# Connector.net
KiCad netlist of a schematic drawn in Altium Designer
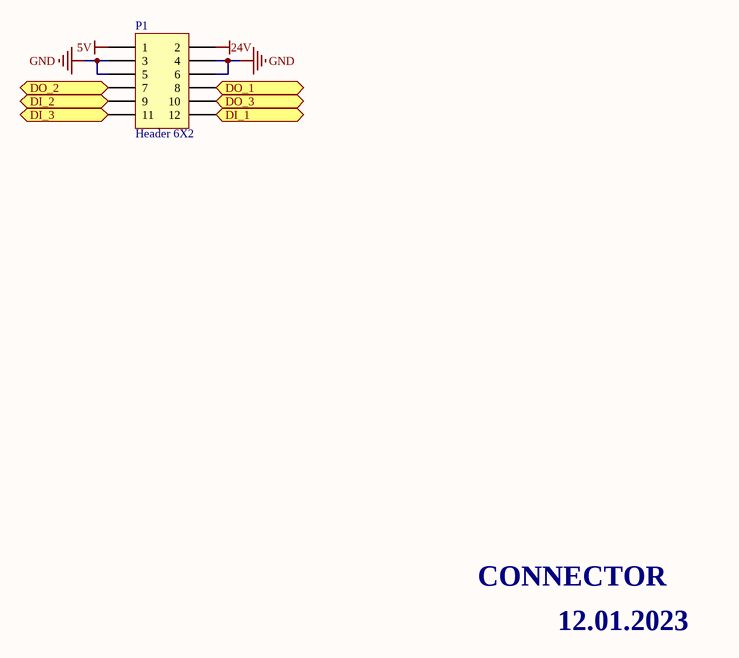
[diagram p0: Connector.SchDoc]

(export (version "E")
  (design (tool "Eeschema 10.0.6"))
  (components
    (comp (ref "P1")
      (value "Header 6X2")
      (footprint "HDR2X6")
      (description "CONNECTOR Header, 6-Pin, Dual row")
      (fields (field (name "PUBLISHER") "Altium Limited"))
      (libsource (lib "geolib") (part "Header 6X2"))
    )
  )
  (nets
    (net (code "1") (name "/DI_1") (class "Default")
      (node (ref "P1") (pin "12") (pinfunction "12_12") (pintype "passive"))
    )
    (net (code "2") (name "/DI_2") (class "Default")
      (node (ref "P1") (pin "9") (pinfunction "9_9") (pintype "passive"))
    )
    (net (code "3") (name "/DI_3") (class "Default")
      (node (ref "P1") (pin "11") (pinfunction "11_11") (pintype "passive"))
    )
    (net (code "4") (name "/DO_1") (class "Default")
      (node (ref "P1") (pin "8") (pinfunction "8_8") (pintype "passive"))
    )
    (net (code "5") (name "/DO_2") (class "Default")
      (node (ref "P1") (pin "7") (pinfunction "7_7") (pintype "passive"))
    )
    (net (code "6") (name "/DO_3") (class "Default")
      (node (ref "P1") (pin "10") (pinfunction "10_10") (pintype "passive"))
    )
    (net (code "7") (name "5V") (class "Default")
      (node (ref "P1") (pin "1") (pinfunction "1_1") (pintype "passive"))
    )
    (net (code "8") (name "24V") (class "Default")
      (node (ref "P1") (pin "2") (pinfunction "2_2") (pintype "passive"))
    )
    (net (code "9") (name "GND") (class "Default")
      (node (ref "P1") (pin "3") (pinfunction "3_3") (pintype "passive"))
      (node (ref "P1") (pin "4") (pinfunction "4_4") (pintype "passive"))
      (node (ref "P1") (pin "5") (pinfunction "5_5") (pintype "passive"))
      (node (ref "P1") (pin "6") (pinfunction "6_6") (pintype "passive"))
    )
  )
)
